# Sheet2.net
KiCad netlist of a schematic drawn in Altium Designer
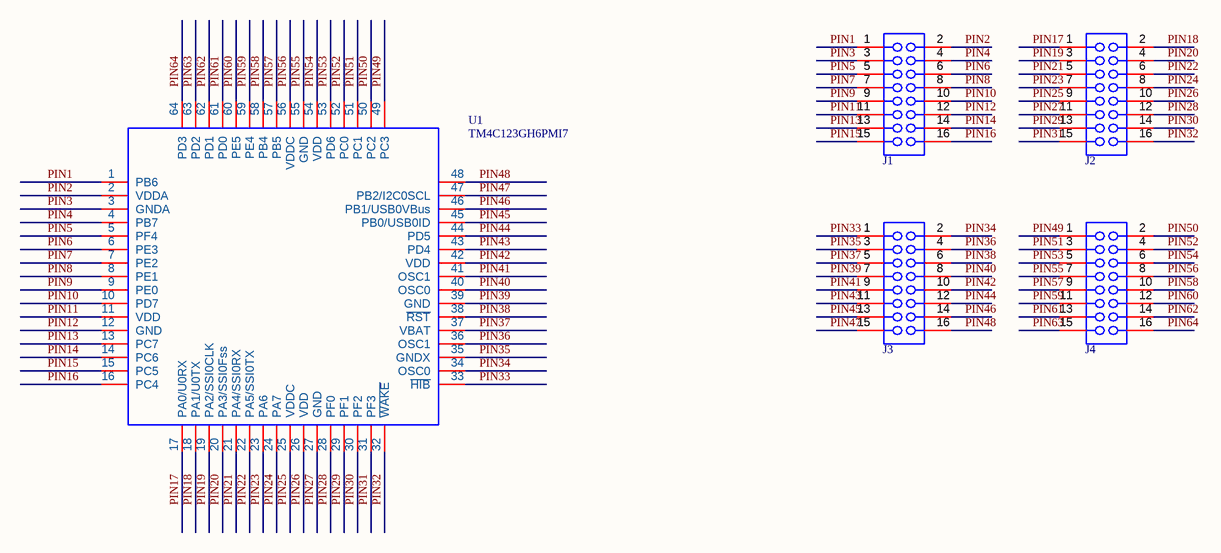
[diagram p0: Sheet2.SchDoc]

(export (version "E")
  (design (tool "Eeschema 10.0.6"))
  (components
    (comp (ref "J1")
      (value "Header 8x2 TH Pitch 2.54mm")
      (footprint "Header 8x2 TH Pitch 2.54mm")
      (libsource (lib "SMDLibrary") (part "Header 8x2 TH Pitch 2.54mm"))
    )
    (comp (ref "J2")
      (value "Header 8x2 TH Pitch 2.54mm")
      (footprint "Header 8x2 TH Pitch 2.54mm")
      (libsource (lib "SMDLibrary") (part "Header 8x2 TH Pitch 2.54mm"))
    )
    (comp (ref "J3")
      (value "Header 8x2 TH Pitch 2.54mm")
      (footprint "Header 8x2 TH Pitch 2.54mm")
      (libsource (lib "SMDLibrary") (part "Header 8x2 TH Pitch 2.54mm"))
    )
    (comp (ref "J4")
      (value "Header 8x2 TH Pitch 2.54mm")
      (footprint "Header 8x2 TH Pitch 2.54mm")
      (libsource (lib "SMDLibrary") (part "Header 8x2 TH Pitch 2.54mm"))
    )
    (comp (ref "U1")
      (value "TM4C123GH6PMI7")
      (footprint "SOCKET-ADAPTER-OTQ-64-05-03")
      (libsource (lib "SMDLibrary") (part "TM4C123GH6PMI7"))
    )
  )
  (nets
    (net (code "1") (name "/PIN1") (class "Default")
      (node (ref "J1") (pin "1") (pinfunction "1_1") (pintype "passive"))
      (node (ref "U1") (pin "1") (pinfunction "PB6_1") (pintype "passive"))
    )
    (net (code "2") (name "/PIN2") (class "Default")
      (node (ref "J1") (pin "2") (pinfunction "2_2") (pintype "passive"))
      (node (ref "U1") (pin "2") (pinfunction "VDDA_2") (pintype "passive"))
    )
    (net (code "3") (name "/PIN3") (class "Default")
      (node (ref "J1") (pin "3") (pinfunction "3_3") (pintype "passive"))
      (node (ref "U1") (pin "3") (pinfunction "GNDA_3") (pintype "passive"))
    )
    (net (code "4") (name "/PIN4") (class "Default")
      (node (ref "J1") (pin "4") (pinfunction "4_4") (pintype "passive"))
      (node (ref "U1") (pin "4") (pinfunction "PB7_4") (pintype "passive"))
    )
    (net (code "5") (name "/PIN5") (class "Default")
      (node (ref "J1") (pin "5") (pinfunction "5_5") (pintype "passive"))
      (node (ref "U1") (pin "5") (pinfunction "PF4_5") (pintype "passive"))
    )
    (net (code "6") (name "/PIN6") (class "Default")
      (node (ref "J1") (pin "6") (pinfunction "6_6") (pintype "passive"))
      (node (ref "U1") (pin "6") (pinfunction "PE3_6") (pintype "passive"))
    )
    (net (code "7") (name "/PIN7") (class "Default")
      (node (ref "J1") (pin "7") (pinfunction "7_7") (pintype "passive"))
      (node (ref "U1") (pin "7") (pinfunction "PE2_7") (pintype "passive"))
    )
    (net (code "8") (name "/PIN8") (class "Default")
      (node (ref "J1") (pin "8") (pinfunction "8_8") (pintype "passive"))
      (node (ref "U1") (pin "8") (pinfunction "PE1_8") (pintype "passive"))
    )
    (net (code "9") (name "/PIN9") (class "Default")
      (node (ref "J1") (pin "9") (pinfunction "9_9") (pintype "passive"))
      (node (ref "U1") (pin "9") (pinfunction "PE0_9") (pintype "passive"))
    )
    (net (code "10") (name "/PIN10") (class "Default")
      (node (ref "J1") (pin "10") (pinfunction "10_10") (pintype "passive"))
      (node (ref "U1") (pin "10") (pinfunction "PD7_10") (pintype "passive"))
    )
    (net (code "11") (name "/PIN11") (class "Default")
      (node (ref "J1") (pin "11") (pinfunction "11_11") (pintype "passive"))
      (node (ref "U1") (pin "11") (pinfunction "VDD_11") (pintype "passive"))
    )
    (net (code "12") (name "/PIN12") (class "Default")
      (node (ref "J1") (pin "12") (pinfunction "12_12") (pintype "passive"))
      (node (ref "U1") (pin "12") (pinfunction "GND_12") (pintype "passive"))
    )
    (net (code "13") (name "/PIN13") (class "Default")
      (node (ref "J1") (pin "13") (pinfunction "13_13") (pintype "passive"))
      (node (ref "U1") (pin "13") (pinfunction "PC7_13") (pintype "passive"))
    )
    (net (code "14") (name "/PIN14") (class "Default")
      (node (ref "J1") (pin "14") (pinfunction "14_14") (pintype "passive"))
      (node (ref "U1") (pin "14") (pinfunction "PC6_14") (pintype "passive"))
    )
    (net (code "15") (name "/PIN15") (class "Default")
      (node (ref "J1") (pin "15") (pinfunction "15_15") (pintype "passive"))
      (node (ref "U1") (pin "15") (pinfunction "PC5_15") (pintype "passive"))
    )
    (net (code "16") (name "/PIN16") (class "Default")
      (node (ref "J1") (pin "16") (pinfunction "16_16") (pintype "passive"))
      (node (ref "U1") (pin "16") (pinfunction "PC4_16") (pintype "passive"))
    )
    (net (code "17") (name "/PIN17") (class "Default")
      (node (ref "J2") (pin "1") (pinfunction "1_1") (pintype "passive"))
      (node (ref "U1") (pin "17") (pinfunction "PA0/U0RX_17") (pintype "passive"))
    )
    (net (code "18") (name "/PIN18") (class "Default")
      (node (ref "J2") (pin "2") (pinfunction "2_2") (pintype "passive"))
      (node (ref "U1") (pin "18") (pinfunction "PA1/U0TX_18") (pintype "passive"))
    )
    (net (code "19") (name "/PIN19") (class "Default")
      (node (ref "J2") (pin "3") (pinfunction "3_3") (pintype "passive"))
      (node (ref "U1") (pin "19") (pinfunction "PA2/SSI0CLK_19") (pintype "passive"))
    )
    (net (code "20") (name "/PIN20") (class "Default")
      (node (ref "J2") (pin "4") (pinfunction "4_4") (pintype "passive"))
      (node (ref "U1") (pin "20") (pinfunction "PA3/SSI0Fss_20") (pintype "passive"))
    )
    (net (code "21") (name "/PIN21") (class "Default")
      (node (ref "J2") (pin "5") (pinfunction "5_5") (pintype "passive"))
      (node (ref "U1") (pin "21") (pinfunction "PA4/SSI0RX_21") (pintype "passive"))
    )
    (net (code "22") (name "/PIN22") (class "Default")
      (node (ref "J2") (pin "6") (pinfunction "6_6") (pintype "passive"))
      (node (ref "U1") (pin "22") (pinfunction "PA5/SSI0TX_22") (pintype "passive"))
    )
    (net (code "23") (name "/PIN23") (class "Default")
      (node (ref "J2") (pin "7") (pinfunction "7_7") (pintype "passive"))
      (node (ref "U1") (pin "23") (pinfunction "PA6_23") (pintype "passive"))
    )
    (net (code "24") (name "/PIN24") (class "Default")
      (node (ref "J2") (pin "8") (pinfunction "8_8") (pintype "passive"))
      (node (ref "U1") (pin "24") (pinfunction "PA7_24") (pintype "passive"))
    )
    (net (code "25") (name "/PIN25") (class "Default")
      (node (ref "J2") (pin "9") (pinfunction "9_9") (pintype "passive"))
      (node (ref "U1") (pin "25") (pinfunction "VDDC_25") (pintype "passive"))
    )
    (net (code "26") (name "/PIN26") (class "Default")
      (node (ref "J2") (pin "10") (pinfunction "10_10") (pintype "passive"))
      (node (ref "U1") (pin "26") (pinfunction "VDD_26") (pintype "passive"))
    )
    (net (code "27") (name "/PIN27") (class "Default")
      (node (ref "J2") (pin "11") (pinfunction "11_11") (pintype "passive"))
      (node (ref "U1") (pin "27") (pinfunction "GND_27") (pintype "passive"))
    )
    (net (code "28") (name "/PIN28") (class "Default")
      (node (ref "J2") (pin "12") (pinfunction "12_12") (pintype "passive"))
      (node (ref "U1") (pin "28") (pinfunction "PF0_28") (pintype "passive"))
    )
    (net (code "29") (name "/PIN29") (class "Default")
      (node (ref "J2") (pin "13") (pinfunction "13_13") (pintype "passive"))
      (node (ref "U1") (pin "29") (pinfunction "PF1_29") (pintype "passive"))
    )
    (net (code "30") (name "/PIN30") (class "Default")
      (node (ref "J2") (pin "14") (pinfunction "14_14") (pintype "passive"))
      (node (ref "U1") (pin "30") (pinfunction "PF2_30") (pintype "passive"))
    )
    (net (code "31") (name "/PIN31") (class "Default")
      (node (ref "J2") (pin "15") (pinfunction "15_15") (pintype "passive"))
      (node (ref "U1") (pin "31") (pinfunction "PF3_31") (pintype "passive"))
    )
    (net (code "32") (name "/PIN32") (class "Default")
      (node (ref "J2") (pin "16") (pinfunction "16_16") (pintype "passive"))
      (node (ref "U1") (pin "32") (pinfunction "~{WAKE}_32") (pintype "passive"))
    )
    (net (code "33") (name "/PIN33") (class "Default")
      (node (ref "J3") (pin "1") (pinfunction "1_1") (pintype "passive"))
      (node (ref "U1") (pin "33") (pinfunction "~{HIB}_33") (pintype "passive"))
    )
    (net (code "34") (name "/PIN34") (class "Default")
      (node (ref "J3") (pin "2") (pinfunction "2_2") (pintype "passive"))
      (node (ref "U1") (pin "34") (pinfunction "OSC0_34") (pintype "passive"))
    )
    (net (code "35") (name "/PIN35") (class "Default")
      (node (ref "J3") (pin "3") (pinfunction "3_3") (pintype "passive"))
      (node (ref "U1") (pin "35") (pinfunction "GNDX_35") (pintype "passive"))
    )
    (net (code "36") (name "/PIN36") (class "Default")
      (node (ref "J3") (pin "4") (pinfunction "4_4") (pintype "passive"))
      (node (ref "U1") (pin "36") (pinfunction "OSC1_36") (pintype "passive"))
    )
    (net (code "37") (name "/PIN37") (class "Default")
      (node (ref "J3") (pin "5") (pinfunction "5_5") (pintype "passive"))
      (node (ref "U1") (pin "37") (pinfunction "VBAT_37") (pintype "passive"))
    )
    (net (code "38") (name "/PIN38") (class "Default")
      (node (ref "J3") (pin "6") (pinfunction "6_6") (pintype "passive"))
      (node (ref "U1") (pin "38") (pinfunction "~{RST}_38") (pintype "passive"))
    )
    (net (code "39") (name "/PIN39") (class "Default")
      (node (ref "J3") (pin "7") (pinfunction "7_7") (pintype "passive"))
      (node (ref "U1") (pin "39") (pinfunction "GND_39") (pintype "passive"))
    )
    (net (code "40") (name "/PIN40") (class "Default")
      (node (ref "J3") (pin "8") (pinfunction "8_8") (pintype "passive"))
      (node (ref "U1") (pin "40") (pinfunction "OSC0_40") (pintype "passive"))
    )
    (net (code "41") (name "/PIN41") (class "Default")
      (node (ref "J3") (pin "9") (pinfunction "9_9") (pintype "passive"))
      (node (ref "U1") (pin "41") (pinfunction "OSC1_41") (pintype "passive"))
    )
    (net (code "42") (name "/PIN42") (class "Default")
      (node (ref "J3") (pin "10") (pinfunction "10_10") (pintype "passive"))
      (node (ref "U1") (pin "42") (pinfunction "VDD_42") (pintype "passive"))
    )
    (net (code "43") (name "/PIN43") (class "Default")
      (node (ref "J3") (pin "11") (pinfunction "11_11") (pintype "passive"))
      (node (ref "U1") (pin "43") (pinfunction "PD4_43") (pintype "passive"))
    )
    (net (code "44") (name "/PIN44") (class "Default")
      (node (ref "J3") (pin "12") (pinfunction "12_12") (pintype "passive"))
      (node (ref "U1") (pin "44") (pinfunction "PD5_44") (pintype "passive"))
    )
    (net (code "45") (name "/PIN45") (class "Default")
      (node (ref "J3") (pin "13") (pinfunction "13_13") (pintype "passive"))
      (node (ref "U1") (pin "45") (pinfunction "PB0/USB0ID_45") (pintype "passive"))
    )
    (net (code "46") (name "/PIN46") (class "Default")
      (node (ref "J3") (pin "14") (pinfunction "14_14") (pintype "passive"))
      (node (ref "U1") (pin "46") (pinfunction "PB1/USB0VBus_46") (pintype "passive"))
    )
    (net (code "47") (name "/PIN47") (class "Default")
      (node (ref "J3") (pin "15") (pinfunction "15_15") (pintype "passive"))
      (node (ref "U1") (pin "47") (pinfunction "PB2/I2C0SCL_47") (pintype "passive"))
    )
    (net (code "48") (name "/PIN48") (class "Default")
      (node (ref "J3") (pin "16") (pinfunction "16_16") (pintype "passive"))
      (node (ref "U1") (pin "48") (pintype "passive"))
    )
    (net (code "49") (name "/PIN49") (class "Default")
      (node (ref "J4") (pin "1") (pinfunction "1_1") (pintype "passive"))
      (node (ref "U1") (pin "49") (pinfunction "PC3_49") (pintype "passive"))
    )
    (net (code "50") (name "/PIN50") (class "Default")
      (node (ref "J4") (pin "2") (pinfunction "2_2") (pintype "passive"))
      (node (ref "U1") (pin "50") (pinfunction "PC2_50") (pintype "passive"))
    )
    (net (code "51") (name "/PIN51") (class "Default")
      (node (ref "J4") (pin "3") (pinfunction "3_3") (pintype "passive"))
      (node (ref "U1") (pin "51") (pinfunction "PC1_51") (pintype "passive"))
    )
    (net (code "52") (name "/PIN52") (class "Default")
      (node (ref "J4") (pin "4") (pinfunction "4_4") (pintype "passive"))
      (node (ref "U1") (pin "52") (pinfunction "PC0_52") (pintype "passive"))
    )
    (net (code "53") (name "/PIN53") (class "Default")
      (node (ref "J4") (pin "5") (pinfunction "5_5") (pintype "passive"))
      (node (ref "U1") (pin "53") (pinfunction "PD6_53") (pintype "passive"))
    )
    (net (code "54") (name "/PIN54") (class "Default")
      (node (ref "J4") (pin "6") (pinfunction "6_6") (pintype "passive"))
      (node (ref "U1") (pin "54") (pinfunction "VDD_54") (pintype "passive"))
    )
    (net (code "55") (name "/PIN55") (class "Default")
      (node (ref "J4") (pin "7") (pinfunction "7_7") (pintype "passive"))
      (node (ref "U1") (pin "55") (pinfunction "GND_55") (pintype "passive"))
    )
    (net (code "56") (name "/PIN56") (class "Default")
      (node (ref "J4") (pin "8") (pinfunction "8_8") (pintype "passive"))
      (node (ref "U1") (pin "56") (pinfunction "VDDC_56") (pintype "passive"))
    )
    (net (code "57") (name "/PIN57") (class "Default")
      (node (ref "J4") (pin "9") (pinfunction "9_9") (pintype "passive"))
      (node (ref "U1") (pin "57") (pinfunction "PB5_57") (pintype "passive"))
    )
    (net (code "58") (name "/PIN58") (class "Default")
      (node (ref "J4") (pin "10") (pinfunction "10_10") (pintype "passive"))
      (node (ref "U1") (pin "58") (pinfunction "PB4_58") (pintype "passive"))
    )
    (net (code "59") (name "/PIN59") (class "Default")
      (node (ref "J4") (pin "11") (pinfunction "11_11") (pintype "passive"))
      (node (ref "U1") (pin "59") (pinfunction "PE4_59") (pintype "passive"))
    )
    (net (code "60") (name "/PIN60") (class "Default")
      (node (ref "J4") (pin "12") (pinfunction "12_12") (pintype "passive"))
      (node (ref "U1") (pin "60") (pinfunction "PE5_60") (pintype "passive"))
    )
    (net (code "61") (name "/PIN61") (class "Default")
      (node (ref "J4") (pin "13") (pinfunction "13_13") (pintype "passive"))
      (node (ref "U1") (pin "61") (pinfunction "PD0_61") (pintype "passive"))
    )
    (net (code "62") (name "/PIN62") (class "Default")
      (node (ref "J4") (pin "14") (pinfunction "14_14") (pintype "passive"))
      (node (ref "U1") (pin "62") (pinfunction "PD1_62") (pintype "passive"))
    )
    (net (code "63") (name "/PIN63") (class "Default")
      (node (ref "J4") (pin "15") (pinfunction "15_15") (pintype "passive"))
      (node (ref "U1") (pin "63") (pinfunction "PD2_63") (pintype "passive"))
    )
    (net (code "64") (name "/PIN64") (class "Default")
      (node (ref "J4") (pin "16") (pinfunction "16_16") (pintype "passive"))
      (node (ref "U1") (pin "64") (pinfunction "PD3_64") (pintype "passive"))
    )
  )
)
